# Root.net
KiCad netlist of a schematic drawn in Altium Designer
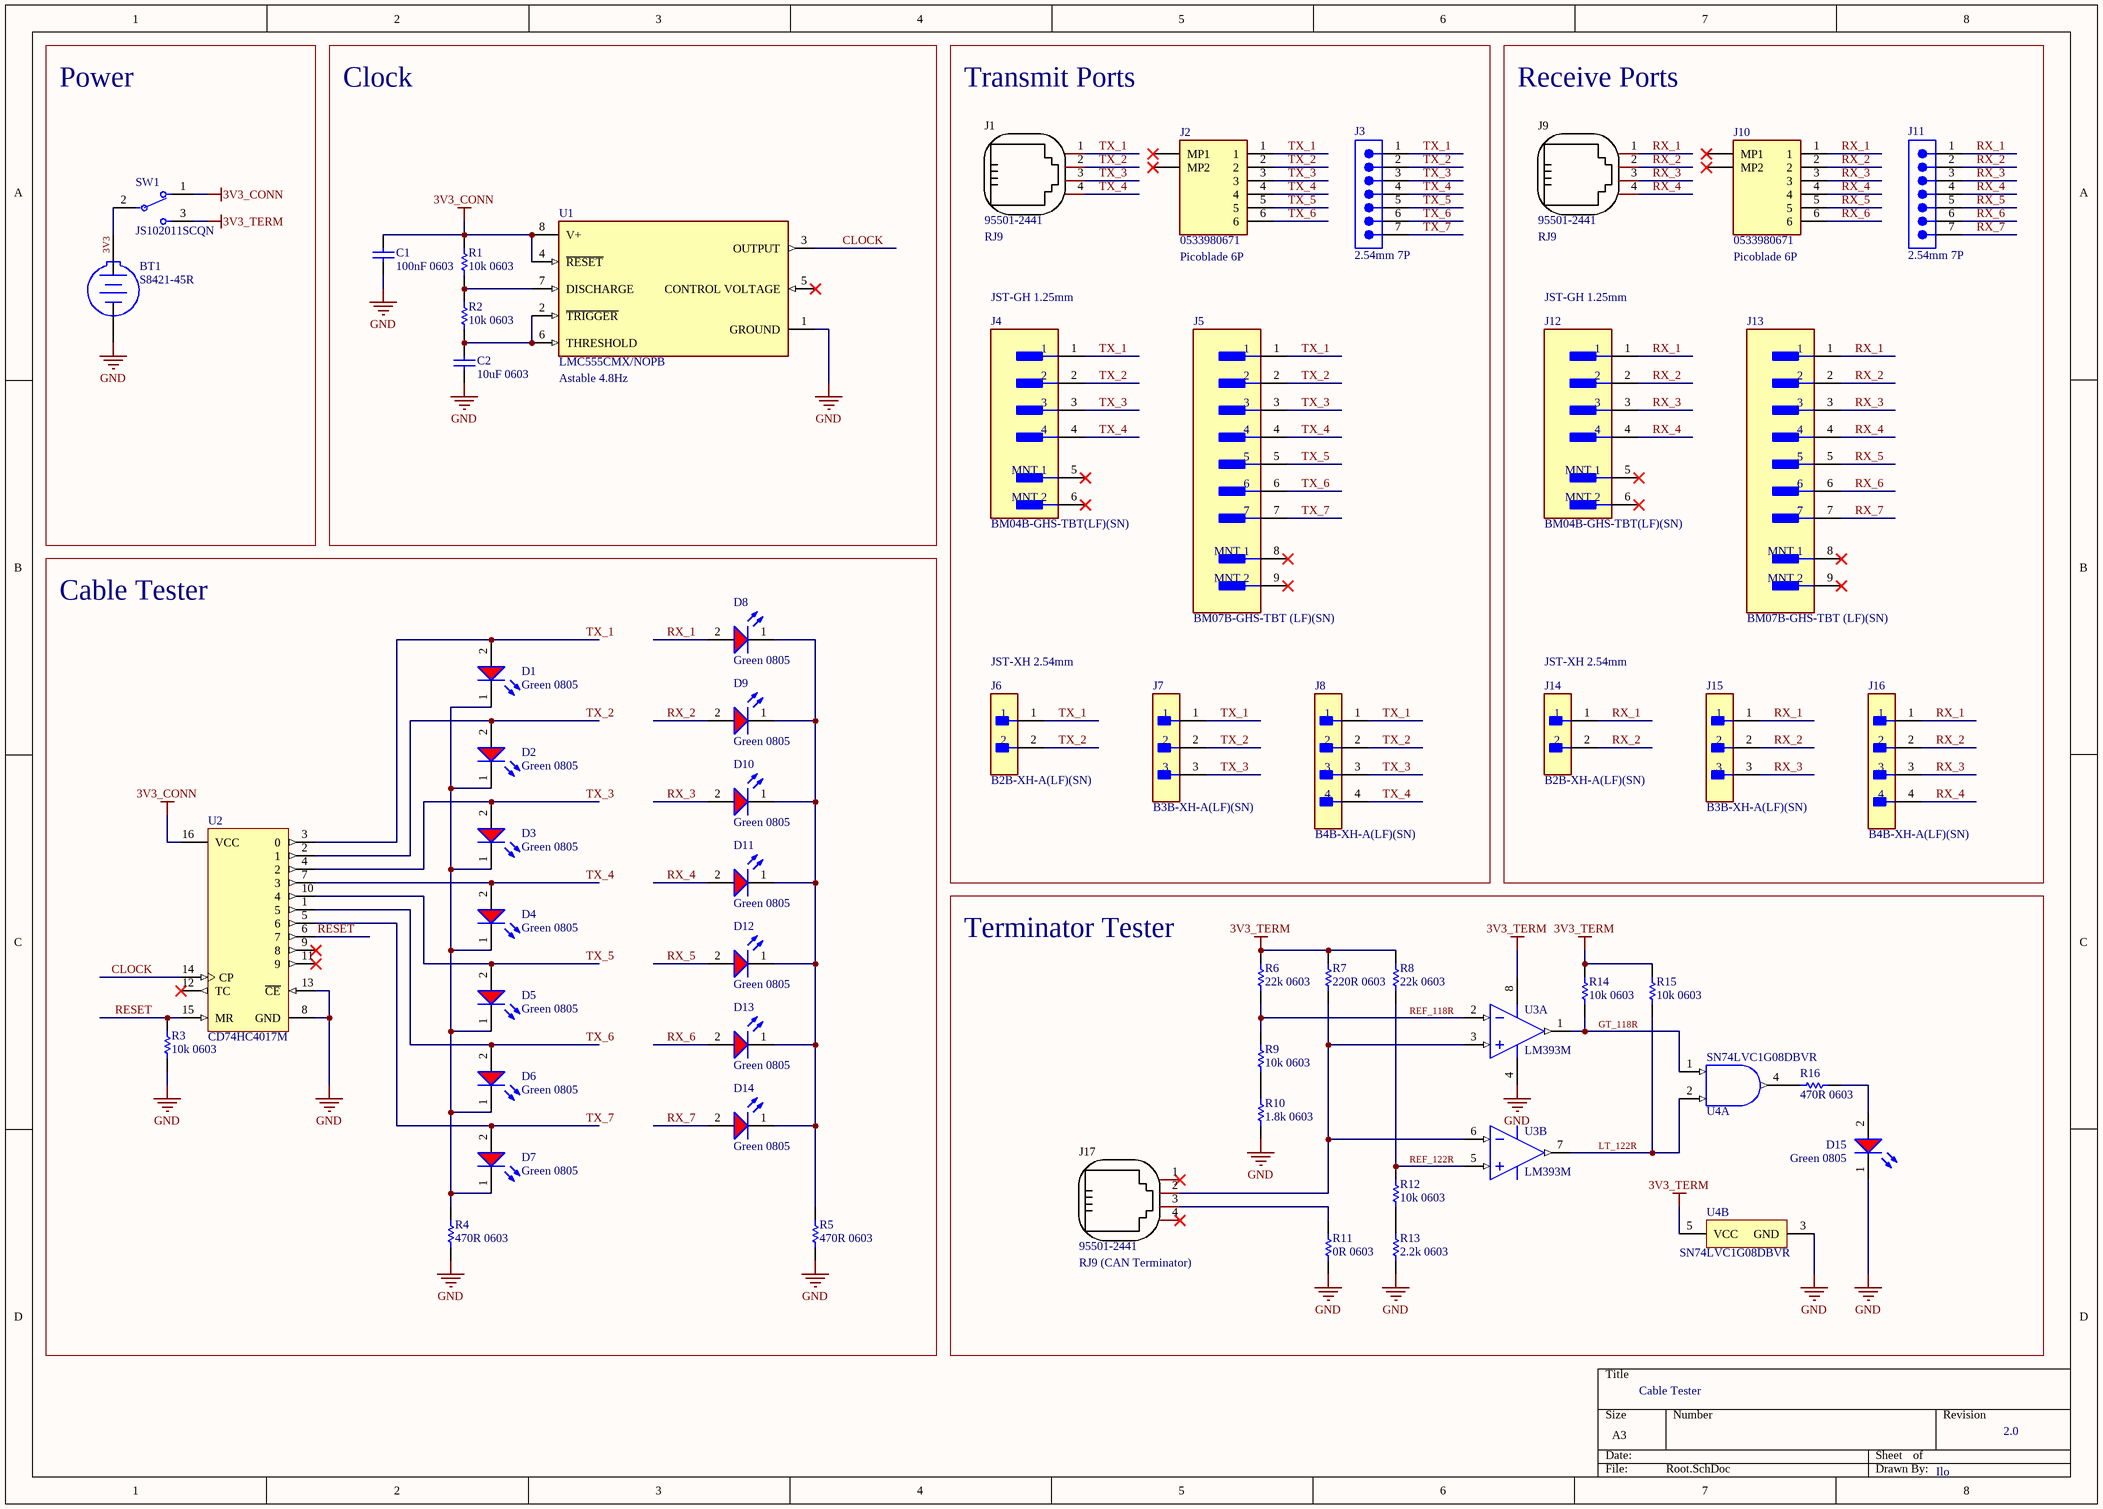
[diagram p0: Root.SchDoc]

(export (version "E")
  (design (tool "Eeschema 10.0.6"))
  (components
    (comp (ref "BT1")
      (value "S8421-45R")
      (footprint "HRWN-S8421-45R_V")
      (description "Bettery Coin Cell Holder, Suitable for CR2032, -40 to 105 degC, 2-Pin SMD, RoHS, Tape and Reel")
      (fields (field (name "MANUFACTURER") "Harwin"))
      (libsource (lib "Altium Content Vault") (part "BATTERY-HOLDER-COIN-2"))
    )
    (comp (ref "C1")
      (value "100nF 0603")
      (footprint "CAPC1608X92X38LL15T08")
      (fields (field (name "MANUFACTURER") "Vitramon") (field (name "PART NUMBER") "VJ0603Y103KXAAC"))
      (libsource (lib "Altium Content Vault") (part "CAP"))
    )
    (comp (ref "C2")
      (value "10uF 0603")
      (footprint "CAPC1608X92X38LL15T08")
      (fields (field (name "MANUFACTURER") "Vitramon") (field (name "PART NUMBER") "VJ0603Y103KXAAC"))
      (libsource (lib "Altium Content Vault") (part "CAP"))
    )
    (comp (ref "D1")
      (value "Green 0805")
      (footprint "WL-SMCW_0805_150080xx75000")
      (description "LED Uni-Color Red 630nm 2-Pin Chip 0805(2012Metric) T/R")
      (libsource (lib "Altium Content Vault") (part "LED_Red_2A-1K"))
    )
    (comp (ref "D2")
      (value "Green 0805")
      (footprint "WL-SMCW_0805_150080xx75000")
      (description "LED Uni-Color Red 630nm 2-Pin Chip 0805(2012Metric) T/R")
      (libsource (lib "Altium Content Vault") (part "LED_Red_2A-1K"))
    )
    (comp (ref "D3")
      (value "Green 0805")
      (footprint "WL-SMCW_0805_150080xx75000")
      (description "LED Uni-Color Red 630nm 2-Pin Chip 0805(2012Metric) T/R")
      (libsource (lib "Altium Content Vault") (part "LED_Red_2A-1K"))
    )
    (comp (ref "D4")
      (value "Green 0805")
      (footprint "WL-SMCW_0805_150080xx75000")
      (description "LED Uni-Color Red 630nm 2-Pin Chip 0805(2012Metric) T/R")
      (libsource (lib "Altium Content Vault") (part "LED_Red_2A-1K"))
    )
    (comp (ref "D5")
      (value "Green 0805")
      (footprint "WL-SMCW_0805_150080xx75000")
      (description "LED Uni-Color Red 630nm 2-Pin Chip 0805(2012Metric) T/R")
      (libsource (lib "Altium Content Vault") (part "LED_Red_2A-1K"))
    )
    (comp (ref "D6")
      (value "Green 0805")
      (footprint "WL-SMCW_0805_150080xx75000")
      (description "LED Uni-Color Red 630nm 2-Pin Chip 0805(2012Metric) T/R")
      (libsource (lib "Altium Content Vault") (part "LED_Red_2A-1K"))
    )
    (comp (ref "D7")
      (value "Green 0805")
      (footprint "WL-SMCW_0805_150080xx75000")
      (description "LED Uni-Color Red 630nm 2-Pin Chip 0805(2012Metric) T/R")
      (libsource (lib "Altium Content Vault") (part "LED_Red_2A-1K"))
    )
    (comp (ref "D8")
      (value "Green 0805")
      (footprint "WL-SMCW_0805_150080xx75000")
      (description "LED Uni-Color Red 630nm 2-Pin Chip 0805(2012Metric) T/R")
      (libsource (lib "Altium Content Vault") (part "LED_Red_2A-1K"))
    )
    (comp (ref "D9")
      (value "Green 0805")
      (footprint "WL-SMCW_0805_150080xx75000")
      (description "LED Uni-Color Red 630nm 2-Pin Chip 0805(2012Metric) T/R")
      (libsource (lib "Altium Content Vault") (part "LED_Red_2A-1K"))
    )
    (comp (ref "D10")
      (value "Green 0805")
      (footprint "WL-SMCW_0805_150080xx75000")
      (description "LED Uni-Color Red 630nm 2-Pin Chip 0805(2012Metric) T/R")
      (libsource (lib "Altium Content Vault") (part "LED_Red_2A-1K"))
    )
    (comp (ref "D11")
      (value "Green 0805")
      (footprint "WL-SMCW_0805_150080xx75000")
      (description "LED Uni-Color Red 630nm 2-Pin Chip 0805(2012Metric) T/R")
      (libsource (lib "Altium Content Vault") (part "LED_Red_2A-1K"))
    )
    (comp (ref "D12")
      (value "Green 0805")
      (footprint "WL-SMCW_0805_150080xx75000")
      (description "LED Uni-Color Red 630nm 2-Pin Chip 0805(2012Metric) T/R")
      (libsource (lib "Altium Content Vault") (part "LED_Red_2A-1K"))
    )
    (comp (ref "D13")
      (value "Green 0805")
      (footprint "WL-SMCW_0805_150080xx75000")
      (description "LED Uni-Color Red 630nm 2-Pin Chip 0805(2012Metric) T/R")
      (libsource (lib "Altium Content Vault") (part "LED_Red_2A-1K"))
    )
    (comp (ref "D14")
      (value "Green 0805")
      (footprint "WL-SMCW_0805_150080xx75000")
      (description "LED Uni-Color Red 630nm 2-Pin Chip 0805(2012Metric) T/R")
      (libsource (lib "Altium Content Vault") (part "LED_Red_2A-1K"))
    )
    (comp (ref "D15")
      (value "Green 0805")
      (footprint "WL-SMCW_0805_150080xx75000")
      (description "LED Uni-Color Red 630nm 2-Pin Chip 0805(2012Metric) T/R")
      (libsource (lib "Altium Content Vault") (part "LED_Red_2A-1K"))
    )
    (comp (ref "J1")
      (value "95501-2441")
      (footprint "RJ45-TH_95501-2441:RJ45-TH_95501-2441")
      (fields (field (name "MANUFACTURER") "MOLEX") (field (name "MANUFACTURER PART") "955012441"))
      (libsource (lib "9550124411_955012441.schdoc") (part "955012441"))
    )
    (comp (ref "J2")
      (value "0533980671")
      (footprint "SamacSys:0533980671")
      (description "Connector")
      (libsource (lib "*") (part "0533980671"))
    )
    (comp (ref "J3")
      (value "2.54mm 7P")
      (footprint "61300711121")
      (libsource (lib "Altium Content Vault") (part "Header_Male_1R_07P"))
    )
    (comp (ref "J4")
      (value "BM04B-GHS-TBT(LF)(SN)")
      (footprint "FP-BM04B-GHS-TBT_LF_SN-MFG")
      (description "CONN HEADER SMD 4POS 1.25MM")
      (libsource (lib "Altium Content Vault") (part "f4320a1371cd6270e33bce1916c33c0"))
    )
    (comp (ref "J5")
      (value "BM07B-GHS-TBT (LF)(SN)")
      (footprint "FP-BM07B-GHS-TBT_LF_SN-MFG")
      (description "CONN HEADER SMD 7POS 1.25MM")
      (libsource (lib "Altium Content Vault") (part "b0abd15a4b949e48c0a2e6945bb7dcd"))
    )
    (comp (ref "J6")
      (value "B2B-XH-A(LF)(SN)")
      (footprint "FP-B2B-XH-A_LF_SN-MFG")
      (description "CONN HEADER VERT 2POS 2.5MM")
      (libsource (lib "Altium Content Vault") (part "3bc925449376181038e59eaffc5286c"))
    )
    (comp (ref "J7")
      (value "B3B-XH-A(LF)(SN)")
      (footprint "FP-B3B-XH-A_LF_SN-MFG")
      (description "CONN HEADER VERT 3POS 2.5MM")
      (fields
        (field (name "OCTOPART") "https://octopart.com/b3b-xh-a%28lf%29%28sn%29-jst-3990185")
        (field (name "MANUFACTURER") "JST")
      )
      (libsource (lib "Altium Content Vault") (part "0d3f023dd272f625e17a2be33dea85f"))
    )
    (comp (ref "J8")
      (value "B4B-XH-A(LF)(SN)")
      (footprint "FP-B4B-XH-A_LF_SN-MFG")
      (description "CONN HEADER VERT 4POS 2.5MM")
      (libsource (lib "Altium Content Vault") (part "299a8cea1bdcbc3624fe62c390fa72c"))
    )
    (comp (ref "J9")
      (value "95501-2441")
      (footprint "RJ45-TH_95501-2441:RJ45-TH_95501-2441")
      (fields (field (name "MANUFACTURER") "MOLEX") (field (name "MANUFACTURER PART") "955012441"))
      (libsource (lib "9550124411_955012441.schdoc") (part "955012441"))
    )
    (comp (ref "J10")
      (value "0533980671")
      (footprint "SamacSys:0533980671")
      (description "Connector")
      (libsource (lib "*") (part "0533980671"))
    )
    (comp (ref "J11")
      (value "2.54mm 7P")
      (footprint "61300711121")
      (libsource (lib "Altium Content Vault") (part "Header_Male_1R_07P"))
    )
    (comp (ref "J12")
      (value "BM04B-GHS-TBT(LF)(SN)")
      (footprint "FP-BM04B-GHS-TBT_LF_SN-MFG")
      (description "CONN HEADER SMD 4POS 1.25MM")
      (libsource (lib "Altium Content Vault") (part "f4320a1371cd6270e33bce1916c33c0"))
    )
    (comp (ref "J13")
      (value "BM07B-GHS-TBT (LF)(SN)")
      (footprint "FP-BM07B-GHS-TBT_LF_SN-MFG")
      (description "CONN HEADER SMD 7POS 1.25MM")
      (libsource (lib "Altium Content Vault") (part "b0abd15a4b949e48c0a2e6945bb7dcd"))
    )
    (comp (ref "J14")
      (value "B2B-XH-A(LF)(SN)")
      (footprint "FP-B2B-XH-A_LF_SN-MFG")
      (description "CONN HEADER VERT 2POS 2.5MM")
      (libsource (lib "Altium Content Vault") (part "3bc925449376181038e59eaffc5286c"))
    )
    (comp (ref "J15")
      (value "B3B-XH-A(LF)(SN)")
      (footprint "FP-B3B-XH-A_LF_SN-MFG")
      (description "CONN HEADER VERT 3POS 2.5MM")
      (fields
        (field (name "OCTOPART") "https://octopart.com/b3b-xh-a%28lf%29%28sn%29-jst-3990185")
        (field (name "MANUFACTURER") "JST")
      )
      (libsource (lib "Altium Content Vault") (part "0d3f023dd272f625e17a2be33dea85f"))
    )
    (comp (ref "J16")
      (value "B4B-XH-A(LF)(SN)")
      (footprint "FP-B4B-XH-A_LF_SN-MFG")
      (description "CONN HEADER VERT 4POS 2.5MM")
      (libsource (lib "Altium Content Vault") (part "299a8cea1bdcbc3624fe62c390fa72c"))
    )
    (comp (ref "J17")
      (value "95501-2441")
      (footprint "RJ45-TH_95501-2441:RJ45-TH_95501-2441")
      (fields (field (name "MANUFACTURER") "MOLEX") (field (name "MANUFACTURER PART") "955012441"))
      (libsource (lib "9550124411_955012441.schdoc") (part "955012441"))
    )
    (comp (ref "R1")
      (value "10k 0603")
      (footprint "RESC0603(1608)_L")
      (description "120R 0.1W 5% 0603 (1608 Metric)  SMD")
      (fields (field (name "POWER") "0.1 W") (field (name "TOLERANCE") "5 %"))
      (libsource (lib "Altium Content Vault") (part "RES"))
    )
    (comp (ref "R2")
      (value "10k 0603")
      (footprint "RESC0603(1608)_L")
      (description "120R 0.1W 5% 0603 (1608 Metric)  SMD")
      (fields (field (name "POWER") "0.1 W") (field (name "TOLERANCE") "5 %"))
      (libsource (lib "Altium Content Vault") (part "RES"))
    )
    (comp (ref "R3")
      (value "10k 0603")
      (footprint "RESC0603(1608)_L")
      (description "120R 0.1W 5% 0603 (1608 Metric)  SMD")
      (fields (field (name "POWER") "0.1 W") (field (name "TOLERANCE") "5 %"))
      (libsource (lib "Altium Content Vault") (part "RES"))
    )
    (comp (ref "R4")
      (value "470R 0603")
      (footprint "RESC0603(1608)_L")
      (description "120R 0.1W 5% 0603 (1608 Metric)  SMD")
      (fields (field (name "POWER") "0.1 W") (field (name "TOLERANCE") "5 %"))
      (libsource (lib "Altium Content Vault") (part "RES"))
    )
    (comp (ref "R5")
      (value "470R 0603")
      (footprint "RESC0603(1608)_L")
      (description "120R 0.1W 5% 0603 (1608 Metric)  SMD")
      (fields (field (name "POWER") "0.1 W") (field (name "TOLERANCE") "5 %"))
      (libsource (lib "Altium Content Vault") (part "RES"))
    )
    (comp (ref "R6")
      (value "22k 0603")
      (footprint "RESC0603(1608)_L")
      (description "120R 0.1W 5% 0603 (1608 Metric)  SMD")
      (fields (field (name "POWER") "0.1 W") (field (name "TOLERANCE") "5 %"))
      (libsource (lib "Altium Content Vault") (part "RES"))
    )
    (comp (ref "R7")
      (value "220R 0603")
      (footprint "RESC0603(1608)_L")
      (description "120R 0.1W 5% 0603 (1608 Metric)  SMD")
      (fields (field (name "POWER") "0.1 W") (field (name "TOLERANCE") "5 %"))
      (libsource (lib "Altium Content Vault") (part "RES"))
    )
    (comp (ref "R8")
      (value "22k 0603")
      (footprint "RESC0603(1608)_L")
      (description "120R 0.1W 5% 0603 (1608 Metric)  SMD")
      (fields (field (name "POWER") "0.1 W") (field (name "TOLERANCE") "5 %"))
      (libsource (lib "Altium Content Vault") (part "RES"))
    )
    (comp (ref "R9")
      (value "10k 0603")
      (footprint "RESC0603(1608)_L")
      (description "120R 0.1W 5% 0603 (1608 Metric)  SMD")
      (fields (field (name "POWER") "0.1 W") (field (name "TOLERANCE") "5 %"))
      (libsource (lib "Altium Content Vault") (part "RES"))
    )
    (comp (ref "R10")
      (value "1.8k 0603")
      (footprint "RESC0603(1608)_L")
      (description "120R 0.1W 5% 0603 (1608 Metric)  SMD")
      (fields (field (name "POWER") "0.1 W") (field (name "TOLERANCE") "5 %"))
      (libsource (lib "Altium Content Vault") (part "RES"))
    )
    (comp (ref "R11")
      (value "0R 0603")
      (footprint "RESC0603(1608)_L")
      (description "120R 0.1W 5% 0603 (1608 Metric)  SMD")
      (fields (field (name "POWER") "0.1 W") (field (name "TOLERANCE") "5 %"))
      (libsource (lib "Altium Content Vault") (part "RES"))
    )
    (comp (ref "R12")
      (value "10k 0603")
      (footprint "RESC0603(1608)_L")
      (description "120R 0.1W 5% 0603 (1608 Metric)  SMD")
      (fields (field (name "POWER") "0.1 W") (field (name "TOLERANCE") "5 %"))
      (libsource (lib "Altium Content Vault") (part "RES"))
    )
    (comp (ref "R13")
      (value "2.2k 0603")
      (footprint "RESC0603(1608)_L")
      (description "120R 0.1W 5% 0603 (1608 Metric)  SMD")
      (fields (field (name "POWER") "0.1 W") (field (name "TOLERANCE") "5 %"))
      (libsource (lib "Altium Content Vault") (part "RES"))
    )
    (comp (ref "R14")
      (value "10k 0603")
      (footprint "RESC0603(1608)_L")
      (description "120R 0.1W 5% 0603 (1608 Metric)  SMD")
      (fields (field (name "POWER") "0.1 W") (field (name "TOLERANCE") "5 %"))
      (libsource (lib "Altium Content Vault") (part "RES"))
    )
    (comp (ref "R15")
      (value "10k 0603")
      (footprint "RESC0603(1608)_L")
      (description "120R 0.1W 5% 0603 (1608 Metric)  SMD")
      (fields (field (name "POWER") "0.1 W") (field (name "TOLERANCE") "5 %"))
      (libsource (lib "Altium Content Vault") (part "RES"))
    )
    (comp (ref "R16")
      (value "470R 0603")
      (footprint "RESC0603(1608)_L")
      (description "120R 0.1W 5% 0603 (1608 Metric)  SMD")
      (fields (field (name "POWER") "0.1 W") (field (name "TOLERANCE") "5 %"))
      (libsource (lib "Altium Content Vault") (part "RES"))
    )
    (comp (ref "SW1")
      (value "JS102011SCQN")
      (footprint "FP-JS102011SCQN-MFG")
      (description "SWITCH SLIDE SPDT 300MA 6V")
      (libsource (lib "Altium Content Vault") (part "39e195cbbadc85d1df0d7eb6847d379"))
    )
    (comp (ref "U1")
      (value "LMC555CMX/NOPB")
      (footprint "FP-D0008A-MFG")
      (description "IC OSC SINGLE TIMER 3MHZ 8-SOIC")
      (fields
        (field (name "OCTOPART") "https://octopart.com/lmc555cmx%2Fnopb-texas+instruments-24815227")
        (field (name "MANUFACTURER") "Texas Instruments")
      )
      (libsource (lib "Altium Content Vault") (part "2d4910f0af3888ed72da4973d42bf58"))
    )
    (comp (ref "U2")
      (value "CD74HC4017M")
      (footprint "D0016A_N")
      (description "High Speed CMOS Logic Decade Counter/Divider with 10 Decoded Outputs, D0016A, TUBE")
      (fields
        (field (name "MANUFACTURER") "Texas Instruments")
        (field (name "GENERIC PART NUMBER") "CD74HC4017")
      )
      (libsource (lib "Altium Content Vault") (part "TI-CD74HC4017-16"))
    )
    (comp (ref "U3")
      (value "LM393M")
      (footprint "D0008A_L")
      (description "Low Power Low Offset Voltage Dual Comparator, 8-pin Narrow SOIC")
      (fields (field (name "MANUFACTURER") "Texas Instruments"))
      (libsource (lib "Altium Content Vault") (part "AN-COMP-LM193-8"))
    )
    (comp (ref "U4")
      (value "SN74LVC1G08DBVR")
      (footprint "DBV0005A_M")
      (description "Single 2-Input Positive-AND Gate, DBV0005A, LARGE T&R")
      (fields
        (field (name "GENERIC PART NUMBER") "SN74LVC1G08")
        (field (name "MANUFACTURER") "Texas Instruments")
      )
      (libsource (lib "Altium Content Vault") (part "TI-SN74XXX1X08-5"))
    )
  )
  (nets
    (net (code "1") (name "/3V3") (class "Default")
      (node (ref "BT1") (pin "1") (pinfunction "+_1") (pintype "passive"))
      (node (ref "SW1") (pin "2") (pinfunction "C_2") (pintype "passive"))
    )
    (net (code "2") (name "/CLOCK") (class "Default")
      (node (ref "U1") (pin "3") (pinfunction "OUTPUT_3") (pintype "output"))
      (node (ref "U2") (pin "14") (pinfunction "CP_14") (pintype "input"))
    )
    (net (code "3") (name "/GT_118R") (class "Default")
      (node (ref "R14") (pin "1") (pinfunction "1_1") (pintype "passive"))
      (node (ref "U3") (pin "1") (pinfunction "OUTA_1") (pintype "output"))
      (node (ref "U4") (pin "1") (pinfunction "A_1") (pintype "input"))
    )
    (net (code "4") (name "/LT_122R") (class "Default")
      (node (ref "R15") (pin "1") (pinfunction "1_1") (pintype "passive"))
      (node (ref "U3") (pin "7") (pinfunction "OUTB_7") (pintype "output"))
      (node (ref "U4") (pin "2") (pinfunction "B_2") (pintype "input"))
    )
    (net (code "5") (name "/REF_118R") (class "Default")
      (node (ref "R6") (pin "1") (pinfunction "1_1") (pintype "passive"))
      (node (ref "R9") (pin "2") (pinfunction "2_2") (pintype "passive"))
      (node (ref "U3") (pin "2") (pinfunction "INA-_2") (pintype "input"))
    )
    (net (code "6") (name "/REF_122R") (class "Default")
      (node (ref "R12") (pin "2") (pinfunction "2_2") (pintype "passive"))
      (node (ref "R8") (pin "1") (pinfunction "1_1") (pintype "passive"))
      (node (ref "U3") (pin "5") (pinfunction "INB+_5") (pintype "input"))
    )
    (net (code "7") (name "/RESET") (class "Default")
      (node (ref "R3") (pin "2") (pinfunction "2_2") (pintype "passive"))
      (node (ref "U2") (pin "15") (pinfunction "MR_15") (pintype "input"))
      (node (ref "U2") (pin "6") (pinfunction "7_6") (pintype "output"))
    )
    (net (code "8") (name "/RX_1") (class "Default")
      (node (ref "D8") (pin "2") (pinfunction "A_2") (pintype "passive"))
      (node (ref "J10") (pin "1") (pinfunction "1_1") (pintype "passive"))
      (node (ref "J11") (pin "1") (pinfunction "1_1") (pintype "passive"))
      (node (ref "J12") (pin "1") (pinfunction "1_1") (pintype "passive"))
      (node (ref "J13") (pin "1") (pinfunction "1_1") (pintype "passive"))
      (node (ref "J14") (pin "1") (pinfunction "1_1") (pintype "passive"))
      (node (ref "J15") (pin "1") (pinfunction "1_1") (pintype "passive"))
      (node (ref "J16") (pin "1") (pinfunction "1_1") (pintype "passive"))
      (node (ref "J9") (pin "1") (pinfunction "1_1") (pintype "passive"))
    )
    (net (code "9") (name "/RX_2") (class "Default")
      (node (ref "D9") (pin "2") (pinfunction "A_2") (pintype "passive"))
      (node (ref "J10") (pin "2") (pinfunction "2_2") (pintype "passive"))
      (node (ref "J11") (pin "2") (pinfunction "2_2") (pintype "passive"))
      (node (ref "J12") (pin "2") (pinfunction "2_2") (pintype "passive"))
      (node (ref "J13") (pin "2") (pinfunction "2_2") (pintype "passive"))
      (node (ref "J14") (pin "2") (pinfunction "2_2") (pintype "passive"))
      (node (ref "J15") (pin "2") (pinfunction "2_2") (pintype "passive"))
      (node (ref "J16") (pin "2") (pinfunction "2_2") (pintype "passive"))
      (node (ref "J9") (pin "2") (pinfunction "2_2") (pintype "passive"))
    )
    (net (code "10") (name "/RX_3") (class "Default")
      (node (ref "D10") (pin "2") (pinfunction "A_2") (pintype "passive"))
      (node (ref "J10") (pin "3") (pinfunction "3_3") (pintype "passive"))
      (node (ref "J11") (pin "3") (pinfunction "3_3") (pintype "passive"))
      (node (ref "J12") (pin "3") (pinfunction "3_3") (pintype "passive"))
      (node (ref "J13") (pin "3") (pinfunction "3_3") (pintype "passive"))
      (node (ref "J15") (pin "3") (pinfunction "3_3") (pintype "passive"))
      (node (ref "J16") (pin "3") (pinfunction "3_3") (pintype "passive"))
      (node (ref "J9") (pin "3") (pinfunction "3_3") (pintype "passive"))
    )
    (net (code "11") (name "/RX_4") (class "Default")
      (node (ref "D11") (pin "2") (pinfunction "A_2") (pintype "passive"))
      (node (ref "J10") (pin "4") (pinfunction "4_4") (pintype "passive"))
      (node (ref "J11") (pin "4") (pinfunction "4_4") (pintype "passive"))
      (node (ref "J12") (pin "4") (pinfunction "4_4") (pintype "passive"))
      (node (ref "J13") (pin "4") (pinfunction "4_4") (pintype "passive"))
      (node (ref "J16") (pin "4") (pinfunction "4_4") (pintype "passive"))
      (node (ref "J9") (pin "4") (pinfunction "4_4") (pintype "passive"))
    )
    (net (code "12") (name "/RX_5") (class "Default")
      (node (ref "D12") (pin "2") (pinfunction "A_2") (pintype "passive"))
      (node (ref "J10") (pin "5") (pinfunction "5_5") (pintype "passive"))
      (node (ref "J11") (pin "5") (pinfunction "5_5") (pintype "passive"))
      (node (ref "J13") (pin "5") (pinfunction "5_5") (pintype "passive"))
    )
    (net (code "13") (name "/RX_6") (class "Default")
      (node (ref "D13") (pin "2") (pinfunction "A_2") (pintype "passive"))
      (node (ref "J10") (pin "6") (pinfunction "6_6") (pintype "passive"))
      (node (ref "J11") (pin "6") (pinfunction "6_6") (pintype "passive"))
      (node (ref "J13") (pin "6") (pinfunction "6_6") (pintype "passive"))
    )
    (net (code "14") (name "/RX_7") (class "Default")
      (node (ref "D14") (pin "2") (pinfunction "A_2") (pintype "passive"))
      (node (ref "J11") (pin "7") (pinfunction "7_7") (pintype "passive"))
      (node (ref "J13") (pin "7") (pinfunction "7_7") (pintype "passive"))
    )
    (net (code "15") (name "/TX_1") (class "Default")
      (node (ref "D1") (pin "2") (pinfunction "A_2") (pintype "passive"))
      (node (ref "J1") (pin "1") (pinfunction "1_1") (pintype "passive"))
      (node (ref "J2") (pin "1") (pinfunction "1_1") (pintype "passive"))
      (node (ref "J3") (pin "1") (pinfunction "1_1") (pintype "passive"))
      (node (ref "J4") (pin "1") (pinfunction "1_1") (pintype "passive"))
      (node (ref "J5") (pin "1") (pinfunction "1_1") (pintype "passive"))
      (node (ref "J6") (pin "1") (pinfunction "1_1") (pintype "passive"))
      (node (ref "J7") (pin "1") (pinfunction "1_1") (pintype "passive"))
      (node (ref "J8") (pin "1") (pinfunction "1_1") (pintype "passive"))
      (node (ref "U2") (pin "3") (pinfunction "0_3") (pintype "output"))
    )
    (net (code "16") (name "/TX_2") (class "Default")
      (node (ref "D2") (pin "2") (pinfunction "A_2") (pintype "passive"))
      (node (ref "J1") (pin "2") (pinfunction "2_2") (pintype "passive"))
      (node (ref "J2") (pin "2") (pinfunction "2_2") (pintype "passive"))
      (node (ref "J3") (pin "2") (pinfunction "2_2") (pintype "passive"))
      (node (ref "J4") (pin "2") (pinfunction "2_2") (pintype "passive"))
      (node (ref "J5") (pin "2") (pinfunction "2_2") (pintype "passive"))
      (node (ref "J6") (pin "2") (pinfunction "2_2") (pintype "passive"))
      (node (ref "J7") (pin "2") (pinfunction "2_2") (pintype "passive"))
      (node (ref "J8") (pin "2") (pinfunction "2_2") (pintype "passive"))
      (node (ref "U2") (pin "2") (pinfunction "1_2") (pintype "output"))
    )
    (net (code "17") (name "/TX_3") (class "Default")
      (node (ref "D3") (pin "2") (pinfunction "A_2") (pintype "passive"))
      (node (ref "J1") (pin "3") (pinfunction "3_3") (pintype "passive"))
      (node (ref "J2") (pin "3") (pinfunction "3_3") (pintype "passive"))
      (node (ref "J3") (pin "3") (pinfunction "3_3") (pintype "passive"))
      (node (ref "J4") (pin "3") (pinfunction "3_3") (pintype "passive"))
      (node (ref "J5") (pin "3") (pinfunction "3_3") (pintype "passive"))
      (node (ref "J7") (pin "3") (pinfunction "3_3") (pintype "passive"))
      (node (ref "J8") (pin "3") (pinfunction "3_3") (pintype "passive"))
      (node (ref "U2") (pin "4") (pinfunction "2_4") (pintype "output"))
    )
    (net (code "18") (name "/TX_4") (class "Default")
      (node (ref "D4") (pin "2") (pinfunction "A_2") (pintype "passive"))
      (node (ref "J1") (pin "4") (pinfunction "4_4") (pintype "passive"))
      (node (ref "J2") (pin "4") (pinfunction "4_4") (pintype "passive"))
      (node (ref "J3") (pin "4") (pinfunction "4_4") (pintype "passive"))
      (node (ref "J4") (pin "4") (pinfunction "4_4") (pintype "passive"))
      (node (ref "J5") (pin "4") (pinfunction "4_4") (pintype "passive"))
      (node (ref "J8") (pin "4") (pinfunction "4_4") (pintype "passive"))
      (node (ref "U2") (pin "7") (pinfunction "3_7") (pintype "output"))
    )
    (net (code "19") (name "/TX_5") (class "Default")
      (node (ref "D5") (pin "2") (pinfunction "A_2") (pintype "passive"))
      (node (ref "J2") (pin "5") (pinfunction "5_5") (pintype "passive"))
      (node (ref "J3") (pin "5") (pinfunction "5_5") (pintype "passive"))
      (node (ref "J5") (pin "5") (pinfunction "5_5") (pintype "passive"))
      (node (ref "U2") (pin "10") (pinfunction "4_10") (pintype "output"))
    )
    (net (code "20") (name "/TX_6") (class "Default")
      (node (ref "D6") (pin "2") (pinfunction "A_2") (pintype "passive"))
      (node (ref "J2") (pin "6") (pinfunction "6_6") (pintype "passive"))
      (node (ref "J3") (pin "6") (pinfunction "6_6") (pintype "passive"))
      (node (ref "J5") (pin "6") (pinfunction "6_6") (pintype "passive"))
      (node (ref "U2") (pin "1") (pinfunction "5_1") (pintype "output"))
    )
    (net (code "21") (name "/TX_7") (class "Default")
      (node (ref "D7") (pin "2") (pinfunction "A_2") (pintype "passive"))
      (node (ref "J3") (pin "7") (pinfunction "7_7") (pintype "passive"))
      (node (ref "J5") (pin "7") (pinfunction "7_7") (pintype "passive"))
      (node (ref "U2") (pin "5") (pinfunction "6_5") (pintype "output"))
    )
    (net (code "22") (name "3V3_CONN") (class "Default")
      (node (ref "C1") (pin "1") (pinfunction "1_1") (pintype "passive"))
      (node (ref "R1") (pin "2") (pinfunction "2_2") (pintype "passive"))
      (node (ref "SW1") (pin "1") (pinfunction "1_1") (pintype "passive"))
      (node (ref "U1") (pin "4") (pinfunction "~{RESET}_4") (pintype "input"))
      (node (ref "U1") (pin "8") (pinfunction "V+_8") (pintype "power_in"))
      (node (ref "U2") (pin "16") (pinfunction "VCC_16") (pintype "power_in"))
    )
    (net (code "23") (name "3V3_TERM") (class "Default")
      (node (ref "R14") (pin "2") (pinfunction "2_2") (pintype "passive"))
      (node (ref "R15") (pin "2") (pinfunction "2_2") (pintype "passive"))
      (node (ref "R6") (pin "2") (pinfunction "2_2") (pintype "passive"))
      (node (ref "R7") (pin "2") (pinfunction "2_2") (pintype "passive"))
      (node (ref "R8") (pin "2") (pinfunction "2_2") (pintype "passive"))
      (node (ref "SW1") (pin "3") (pinfunction "3_3") (pintype "passive"))
      (node (ref "U3") (pin "8") (pinfunction "V+_8") (pintype "power_in"))
      (node (ref "U4") (pin "5") (pinfunction "VCC_5") (pintype "power_in"))
    )
    (net (code "24") (name "GND") (class "Default")
      (node (ref "BT1") (pin "2") (pinfunction "-_2") (pintype "passive"))
      (node (ref "C1") (pin "2") (pinfunction "2_2") (pintype "passive"))
      (node (ref "C2") (pin "2") (pinfunction "2_2") (pintype "passive"))
      (node (ref "D15") (pin "1") (pinfunction "K_1") (pintype "passive"))
      (node (ref "R10") (pin "1") (pinfunction "1_1") (pintype "passive"))
      (node (ref "R11") (pin "1") (pinfunction "1_1") (pintype "passive"))
      (node (ref "R13") (pin "1") (pinfunction "1_1") (pintype "passive"))
      (node (ref "R3") (pin "1") (pinfunction "1_1") (pintype "passive"))
      (node (ref "R4") (pin "1") (pinfunction "1_1") (pintype "passive"))
      (node (ref "R5") (pin "1") (pinfunction "1_1") (pintype "passive"))
      (node (ref "U1") (pin "1") (pinfunction "GROUND_1") (pintype "power_in"))
      (node (ref "U2") (pin "13") (pinfunction "~{CE}_13") (pintype "input"))
      (node (ref "U2") (pin "8") (pinfunction "GND_8") (pintype "power_in"))
      (node (ref "U3") (pin "4") (pinfunction "GND_4") (pintype "power_in"))
      (node (ref "U4") (pin "3") (pinfunction "GND_3") (pintype "power_in"))
    )
    (net (code "25") (name "Net-(D1-K)") (class "Default")
      (node (ref "D1") (pin "1") (pinfunction "K_1") (pintype "passive"))
      (node (ref "D2") (pin "1") (pinfunction "K_1") (pintype "passive"))
      (node (ref "D3") (pin "1") (pinfunction "K_1") (pintype "passive"))
      (node (ref "D4") (pin "1") (pinfunction "K_1") (pintype "passive"))
      (node (ref "D5") (pin "1") (pinfunction "K_1") (pintype "passive"))
      (node (ref "D6") (pin "1") (pinfunction "K_1") (pintype "passive"))
      (node (ref "D7") (pin "1") (pinfunction "K_1") (pintype "passive"))
      (node (ref "R4") (pin "2") (pinfunction "2_2") (pintype "passive"))
    )
    (net (code "26") (name "Net-(D10-K)") (class "Default")
      (node (ref "D10") (pin "1") (pinfunction "K_1") (pintype "passive"))
      (node (ref "D11") (pin "1") (pinfunction "K_1") (pintype "passive"))
      (node (ref "D12") (pin "1") (pinfunction "K_1") (pintype "passive"))
      (node (ref "D13") (pin "1") (pinfunction "K_1") (pintype "passive"))
      (node (ref "D14") (pin "1") (pinfunction "K_1") (pintype "passive"))
      (node (ref "D8") (pin "1") (pinfunction "K_1") (pintype "passive"))
      (node (ref "D9") (pin "1") (pinfunction "K_1") (pintype "passive"))
      (node (ref "R5") (pin "2") (pinfunction "2_2") (pintype "passive"))
    )
    (net (code "27") (name "Net-(D15-A)") (class "Default")
      (node (ref "D15") (pin "2") (pinfunction "A_2") (pintype "passive"))
      (node (ref "R16") (pin "1") (pinfunction "1_1") (pintype "passive"))
    )
    (net (code "28") (name "Net-(J17-Pad3)") (class "Default")
      (node (ref "J17") (pin "3") (pinfunction "3_3") (pintype "passive"))
      (node (ref "R11") (pin "2") (pinfunction "2_2") (pintype "passive"))
    )
    (net (code "29") (name "Net-(R10-Pad2)") (class "Default")
      (node (ref "R10") (pin "2") (pinfunction "2_2") (pintype "passive"))
      (node (ref "R9") (pin "1") (pinfunction "1_1") (pintype "passive"))
    )
    (net (code "30") (name "Net-(R12-Pad1)") (class "Default")
      (node (ref "R12") (pin "1") (pinfunction "1_1") (pintype "passive"))
      (node (ref "R13") (pin "2") (pinfunction "2_2") (pintype "passive"))
    )
    (net (code "31") (name "Net-(U1-DISCHARGE)") (class "Default")
      (node (ref "R1") (pin "1") (pinfunction "1_1") (pintype "passive"))
      (node (ref "R2") (pin "2") (pinfunction "2_2") (pintype "passive"))
      (node (ref "U1") (pin "7") (pinfunction "DISCHARGE_7") (pintype "input"))
    )
    (net (code "32") (name "Net-(U1-THRESHOLD)") (class "Default")
      (node (ref "C2") (pin "1") (pinfunction "1_1") (pintype "passive"))
      (node (ref "R2") (pin "1") (pinfunction "1_1") (pintype "passive"))
      (node (ref "U1") (pin "2") (pinfunction "~{TRIGGER}_2") (pintype "input"))
      (node (ref "U1") (pin "6") (pinfunction "THRESHOLD_6") (pintype "input"))
    )
    (net (code "33") (name "Net-(U3A-INA+)") (class "Default")
      (node (ref "J17") (pin "2") (pinfunction "2_2") (pintype "passive"))
      (node (ref "R7") (pin "1") (pinfunction "1_1") (pintype "passive"))
      (node (ref "U3") (pin "3") (pinfunction "INA+_3") (pintype "input"))
      (node (ref "U3") (pin "6") (pinfunction "INB-_6") (pintype "input"))
    )
    (net (code "34") (name "Net-(U4A-Y)") (class "Default")
      (node (ref "R16") (pin "2") (pinfunction "2_2") (pintype "passive"))
      (node (ref "U4") (pin "4") (pinfunction "Y_4") (pintype "output"))
    )
    (net (code "35") (name "unconnected-(J2-PadMP1)") (class "Default")
      (node (ref "J2") (pin "MP1") (pinfunction "MP1_MP1") (pintype "passive+no_connect"))
    )
    (net (code "36") (name "unconnected-(J2-PadMP2)") (class "Default")
      (node (ref "J2") (pin "MP2") (pinfunction "MP2_MP2") (pintype "passive+no_connect"))
    )
    (net (code "37") (name "unconnected-(J4-MNT_1-Pad5)") (class "Default")
      (node (ref "J4") (pin "5") (pinfunction "MNT_1_5") (pintype "passive+no_connect"))
    )
    (net (code "38") (name "unconnected-(J4-MNT_2-Pad6)") (class "Default")
      (node (ref "J4") (pin "6") (pinfunction "MNT_2_6") (pintype "passive+no_connect"))
    )
    (net (code "39") (name "unconnected-(J5-MNT_1-Pad8)") (class "Default")
      (node (ref "J5") (pin "8") (pinfunction "MNT_1_8") (pintype "passive+no_connect"))
    )
    (net (code "40") (name "unconnected-(J5-MNT_2-Pad9)") (class "Default")
      (node (ref "J5") (pin "9") (pinfunction "MNT_2_9") (pintype "passive+no_connect"))
    )
    (net (code "41") (name "unconnected-(J10-PadMP1)") (class "Default")
      (node (ref "J10") (pin "MP1") (pinfunction "MP1_MP1") (pintype "passive+no_connect"))
    )
    (net (code "42") (name "unconnected-(J10-PadMP2)") (class "Default")
      (node (ref "J10") (pin "MP2") (pinfunction "MP2_MP2") (pintype "passive+no_connect"))
    )
    (net (code "43") (name "unconnected-(J12-MNT_1-Pad5)") (class "Default")
      (node (ref "J12") (pin "5") (pinfunction "MNT_1_5") (pintype "passive+no_connect"))
    )
    (net (code "44") (name "unconnected-(J12-MNT_2-Pad6)") (class "Default")
      (node (ref "J12") (pin "6") (pinfunction "MNT_2_6") (pintype "passive+no_connect"))
    )
    (net (code "45") (name "unconnected-(J13-MNT_1-Pad8)") (class "Default")
      (node (ref "J13") (pin "8") (pinfunction "MNT_1_8") (pintype "passive+no_connect"))
    )
    (net (code "46") (name "unconnected-(J13-MNT_2-Pad9)") (class "Default")
      (node (ref "J13") (pin "9") (pinfunction "MNT_2_9") (pintype "passive+no_connect"))
    )
    (net (code "47") (name "unconnected-(J17-Pad1)") (class "Default")
      (node (ref "J17") (pin "1") (pinfunction "1_1") (pintype "passive+no_connect"))
    )
    (net (code "48") (name "unconnected-(J17-Pad4)") (class "Default")
      (node (ref "J17") (pin "4") (pinfunction "4_4") (pintype "passive+no_connect"))
    )
    (net (code "49") (name "unconnected-(U1-CONTROL_VOLTAGE-Pad5)") (class "Default")
      (node (ref "U1") (pin "5") (pinfunction "CONTROL_VOLTAGE_5") (pintype "input+no_connect"))
    )
    (net (code "50") (name "unconnected-(U2-8-Pad9)") (class "Default")
      (node (ref "U2") (pin "9") (pinfunction "8_9") (pintype "output+no_connect"))
    )
    (net (code "51") (name "unconnected-(U2-9-Pad11)") (class "Default")
      (node (ref "U2") (pin "11") (pinfunction "9_11") (pintype "output+no_connect"))
    )
    (net (code "52") (name "unconnected-(U2-TC-Pad12)") (class "Default")
      (node (ref "U2") (pin "12") (pinfunction "TC_12") (pintype "output+no_connect"))
    )
  )
)
